# USB-6002-breakout-DIO.net
KiCad netlist of a schematic drawn in EAGLE
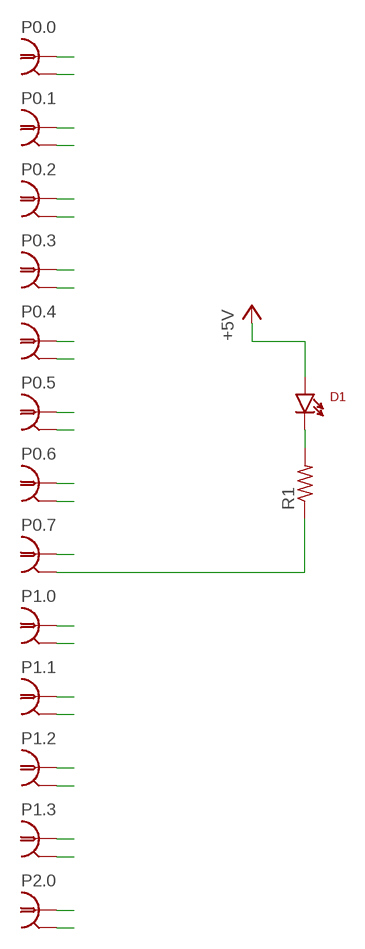
[diagram p0: schematic, sheet 1]

(export (version "E")
  (design (tool "Eeschema 10.0.6"))
  (components
    (comp (ref "D1")
      (value "LED/MINI-IND")
      (footprint "eagle-import:HLMP--F0010")
      (libsource (lib "eagle-import") (part "LED/MINI-IND"))
    )
    (comp (ref "P0.0")
      (value "BNC-V")
      (footprint "eagle-import:BNC-V")
      (libsource (lib "eagle-import") (part "BNC-V"))
    )
    (comp (ref "P0.1")
      (value "BNC-V")
      (footprint "eagle-import:BNC-V")
      (libsource (lib "eagle-import") (part "BNC-V"))
    )
    (comp (ref "P0.2")
      (value "BNC-V")
      (footprint "eagle-import:BNC-V")
      (libsource (lib "eagle-import") (part "BNC-V"))
    )
    (comp (ref "P0.3")
      (value "BNC-V")
      (footprint "eagle-import:BNC-V")
      (libsource (lib "eagle-import") (part "BNC-V"))
    )
    (comp (ref "P0.4")
      (value "BNC-V")
      (footprint "eagle-import:BNC-V")
      (libsource (lib "eagle-import") (part "BNC-V"))
    )
    (comp (ref "P0.5")
      (value "BNC-V")
      (footprint "eagle-import:BNC-V")
      (libsource (lib "eagle-import") (part "BNC-V"))
    )
    (comp (ref "P0.6")
      (value "BNC-V")
      (footprint "eagle-import:BNC-V")
      (libsource (lib "eagle-import") (part "BNC-V"))
    )
    (comp (ref "P0.7")
      (value "BNC-V")
      (footprint "eagle-import:BNC-V")
      (libsource (lib "eagle-import") (part "BNC-V"))
    )
    (comp (ref "P1.0")
      (value "BNC-V")
      (footprint "eagle-import:BNC-V")
      (libsource (lib "eagle-import") (part "BNC-V"))
    )
    (comp (ref "P1.1")
      (value "BNC-V")
      (footprint "eagle-import:BNC-V")
      (libsource (lib "eagle-import") (part "BNC-V"))
    )
    (comp (ref "P1.2")
      (value "BNC-V")
      (footprint "eagle-import:BNC-V")
      (libsource (lib "eagle-import") (part "BNC-V"))
    )
    (comp (ref "P1.3")
      (value "BNC-V")
      (footprint "eagle-import:BNC-V")
      (libsource (lib "eagle-import") (part "BNC-V"))
    )
    (comp (ref "P2.0")
      (value "BNC-V")
      (footprint "eagle-import:BNC-V")
      (libsource (lib "eagle-import") (part "BNC-V"))
    )
    (comp (ref "R1")
      (value "R-US_M1206")
      (footprint "eagle-import:M1206")
      (libsource (lib "eagle-import") (part "R-US_M1206"))
    )
  )
  (nets
    (net (code "1") (name "+5V") (class "Default")
      (node (ref "D1") (pin "A") (pinfunction "A_A") (pintype "bidirectional"))
    )
    (net (code "2") (name "/DGND") (class "Default")
      (node (ref "P0.0") (pin "2") (pinfunction "2_2") (pintype "passive"))
      (node (ref "P0.1") (pin "2") (pinfunction "2_2") (pintype "passive"))
      (node (ref "P0.2") (pin "2") (pinfunction "2_2") (pintype "passive"))
      (node (ref "P0.3") (pin "2") (pinfunction "2_2") (pintype "passive"))
      (node (ref "P0.4") (pin "2") (pinfunction "2_2") (pintype "passive"))
      (node (ref "P0.5") (pin "2") (pinfunction "2_2") (pintype "passive"))
      (node (ref "P0.6") (pin "2") (pinfunction "2_2") (pintype "passive"))
      (node (ref "P0.7") (pin "2") (pinfunction "2_2") (pintype "passive"))
      (node (ref "P1.0") (pin "2") (pinfunction "2_2") (pintype "passive"))
      (node (ref "P1.1") (pin "2") (pinfunction "2_2") (pintype "passive"))
      (node (ref "P1.2") (pin "2") (pinfunction "2_2") (pintype "passive"))
      (node (ref "P1.3") (pin "2") (pinfunction "2_2") (pintype "passive"))
      (node (ref "P2.0") (pin "2") (pinfunction "2_2") (pintype "passive"))
      (node (ref "R1") (pin "1") (pinfunction "1_1") (pintype "passive"))
    )
    (net (code "3") (name "Net-(D1-PadC)") (class "Default")
      (node (ref "D1") (pin "C") (pinfunction "C_C") (pintype "bidirectional"))
      (node (ref "R1") (pin "2") (pinfunction "2_2") (pintype "passive"))
    )
    (net (code "4") (name "unconnected-(P0.0-Pad1)") (class "Default")
      (node (ref "P0.0") (pin "1") (pinfunction "1_1") (pintype "passive"))
    )
    (net (code "5") (name "unconnected-(P0.1-Pad1)") (class "Default")
      (node (ref "P0.1") (pin "1") (pinfunction "1_1") (pintype "passive"))
    )
    (net (code "6") (name "unconnected-(P0.2-Pad1)") (class "Default")
      (node (ref "P0.2") (pin "1") (pinfunction "1_1") (pintype "passive"))
    )
    (net (code "7") (name "unconnected-(P0.3-Pad1)") (class "Default")
      (node (ref "P0.3") (pin "1") (pinfunction "1_1") (pintype "passive"))
    )
    (net (code "8") (name "unconnected-(P0.4-Pad1)") (class "Default")
      (node (ref "P0.4") (pin "1") (pinfunction "1_1") (pintype "passive"))
    )
    (net (code "9") (name "unconnected-(P0.5-Pad1)") (class "Default")
      (node (ref "P0.5") (pin "1") (pinfunction "1_1") (pintype "passive"))
    )
    (net (code "10") (name "unconnected-(P0.6-Pad1)") (class "Default")
      (node (ref "P0.6") (pin "1") (pinfunction "1_1") (pintype "passive"))
    )
    (net (code "11") (name "unconnected-(P0.7-Pad1)") (class "Default")
      (node (ref "P0.7") (pin "1") (pinfunction "1_1") (pintype "passive"))
    )
    (net (code "12") (name "unconnected-(P1.0-Pad1)") (class "Default")
      (node (ref "P1.0") (pin "1") (pinfunction "1_1") (pintype "passive"))
    )
    (net (code "13") (name "unconnected-(P1.1-Pad1)") (class "Default")
      (node (ref "P1.1") (pin "1") (pinfunction "1_1") (pintype "passive"))
    )
    (net (code "14") (name "unconnected-(P1.2-Pad1)") (class "Default")
      (node (ref "P1.2") (pin "1") (pinfunction "1_1") (pintype "passive"))
    )
    (net (code "15") (name "unconnected-(P1.3-Pad1)") (class "Default")
      (node (ref "P1.3") (pin "1") (pinfunction "1_1") (pintype "passive"))
    )
    (net (code "16") (name "unconnected-(P2.0-Pad1)") (class "Default")
      (node (ref "P2.0") (pin "1") (pinfunction "1_1") (pintype "passive"))
    )
  )
)
